# Schematic_OpenBook.net
KiCad netlist of a schematic drawn in EAGLE
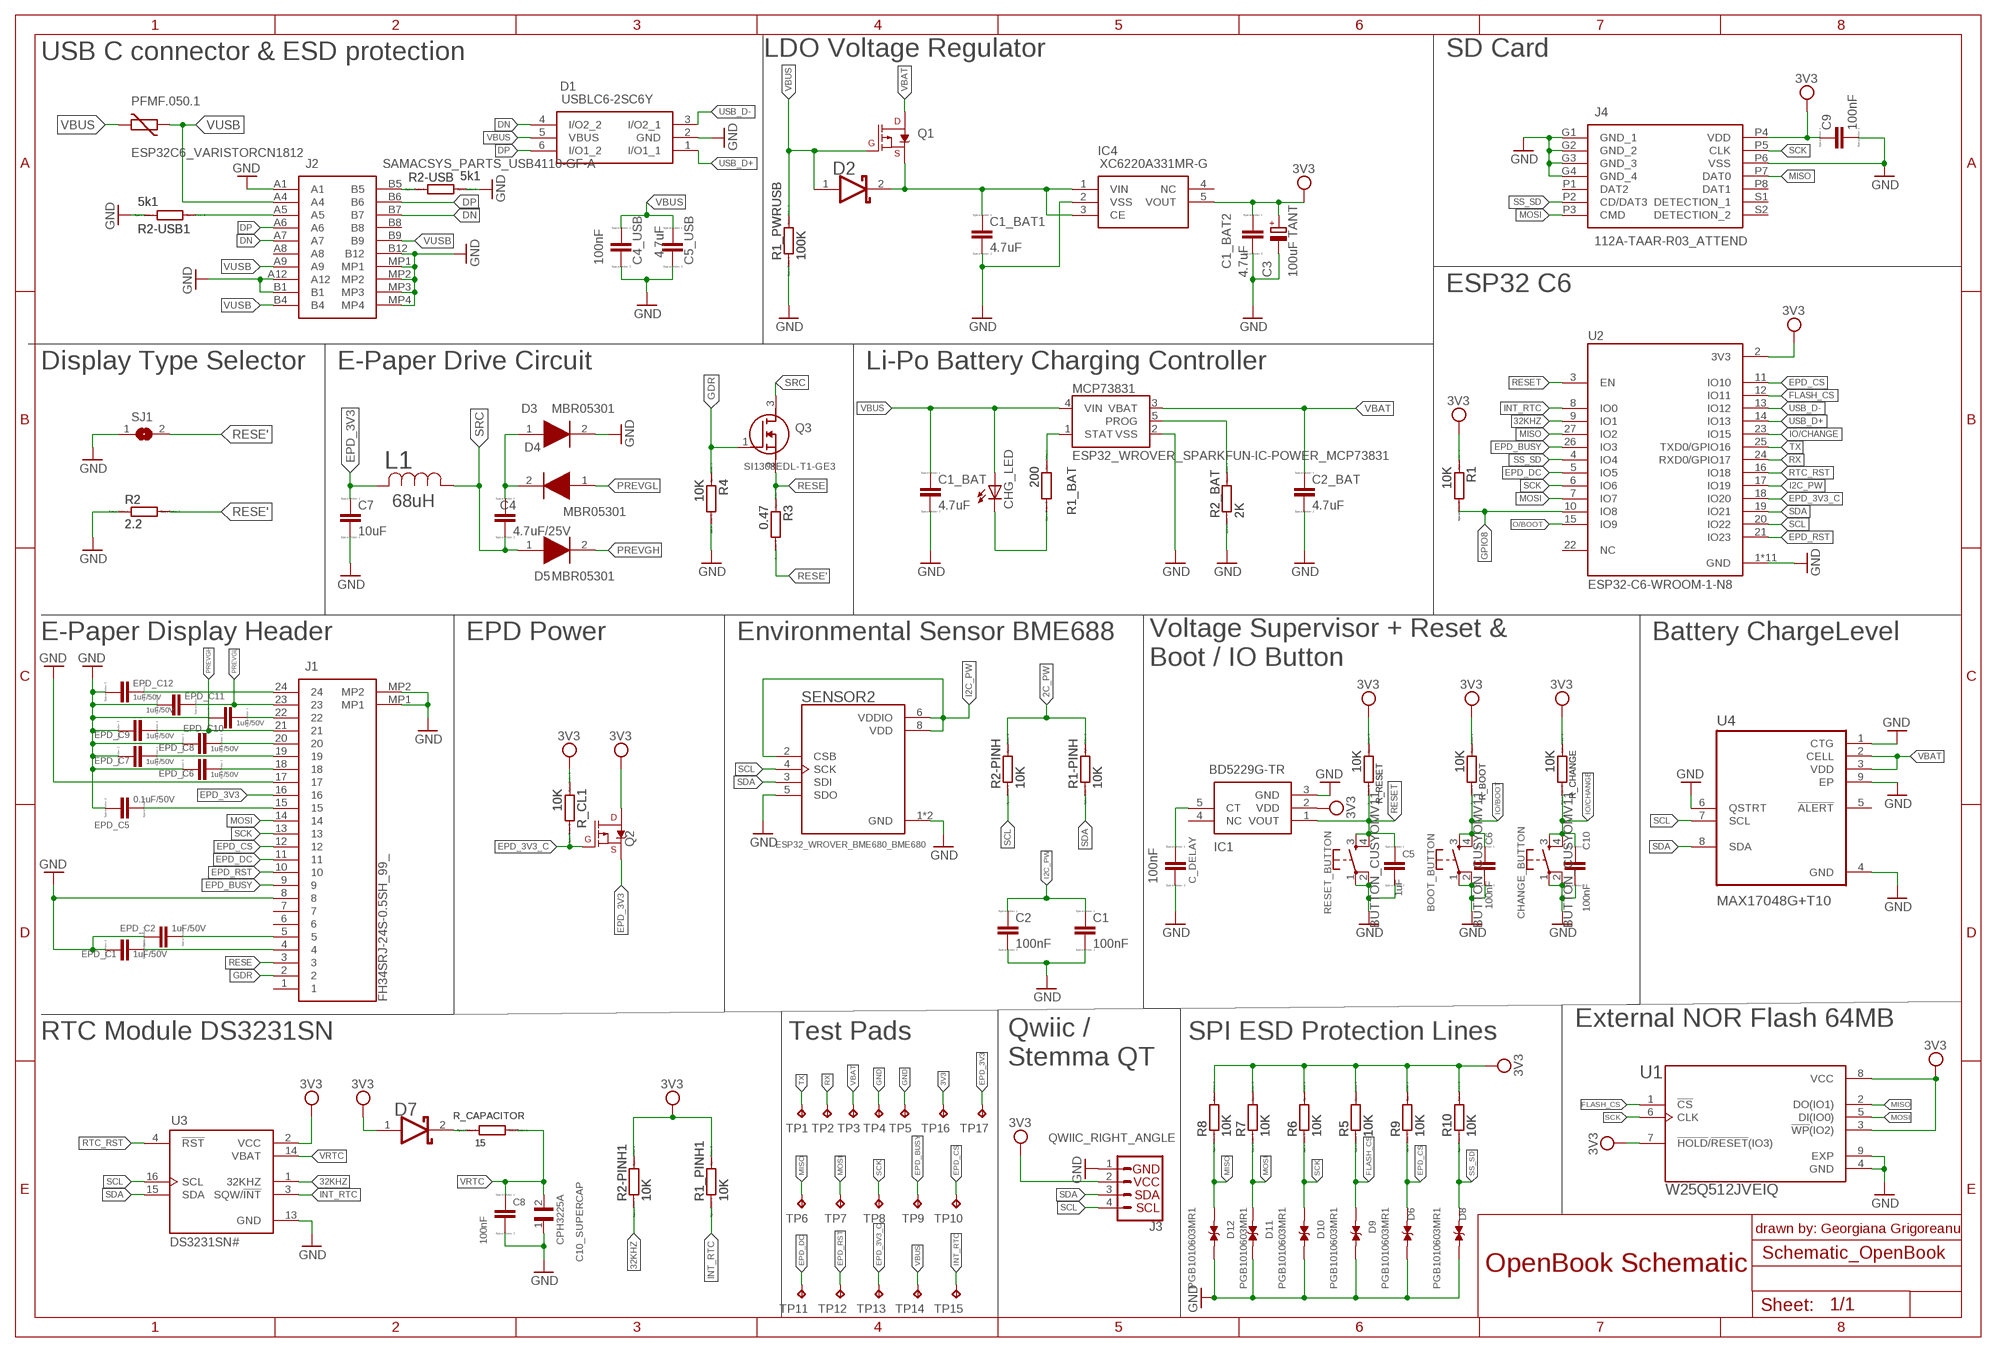
[diagram p0: schematic, sheet 1]

(export (version "E")
  (design (tool "Eeschema 10.0.6"))
  (components
    (comp (ref "BOOT_BUTTON")
      (value "BUTTON_CUSYOMV11")
      (footprint "eagle-import:MYBUTTON")
      (libsource (lib "eagle-import") (part "BUTTON_CUSYOMV11"))
    )
    (comp (ref "C1")
      (value "100nF")
      (footprint "eagle-import:ESP32_WROVER_EAGLE-LTSPICE_C0402")
      (libsource (lib "eagle-import") (part "ESP32_WROVER_EAGLE-LTSPICE_C"))
    )
    (comp (ref "C1_BAT")
      (value "4.7uF")
      (footprint "eagle-import:ESP32_WROVER_EAGLE-LTSPICE_C0402")
      (libsource (lib "eagle-import") (part "ESP32_WROVER_EAGLE-LTSPICE_C"))
    )
    (comp (ref "C1_BAT1")
      (value "4.7uF")
      (footprint "eagle-import:ESP32_WROVER_EAGLE-LTSPICE_C0402")
      (libsource (lib "eagle-import") (part "ESP32_WROVER_EAGLE-LTSPICE_C"))
    )
    (comp (ref "C1_BAT2")
      (value "4.7uF")
      (footprint "eagle-import:ESP32_WROVER_EAGLE-LTSPICE_C0402")
      (libsource (lib "eagle-import") (part "ESP32_WROVER_EAGLE-LTSPICE_C"))
    )
    (comp (ref "C2")
      (value "100nF")
      (footprint "eagle-import:ESP32_WROVER_EAGLE-LTSPICE_C0402")
      (libsource (lib "eagle-import") (part "ESP32_WROVER_EAGLE-LTSPICE_C"))
    )
    (comp (ref "C2_BAT")
      (value "4.7uF")
      (footprint "eagle-import:ESP32_WROVER_EAGLE-LTSPICE_C0402")
      (libsource (lib "eagle-import") (part "ESP32_WROVER_EAGLE-LTSPICE_C"))
    )
    (comp (ref "C3")
      (value "100uF TANT")
      (footprint "eagle-import:RCL_CT3528")
      (libsource (lib "eagle-import") (part "RCL_CPOL-EUCT3528"))
    )
    (comp (ref "C4")
      (value "4.7uF/25V")
      (footprint "eagle-import:ESP32_WROVER_EAGLE-LTSPICE_C0402")
      (libsource (lib "eagle-import") (part "ESP32_WROVER_EAGLE-LTSPICE_C"))
    )
    (comp (ref "C4_USB")
      (value "100nF")
      (footprint "eagle-import:ESP32_WROVER_EAGLE-LTSPICE_C0402")
      (libsource (lib "eagle-import") (part "ESP32_WROVER_EAGLE-LTSPICE_C"))
    )
    (comp (ref "C5")
      (value "1uF")
      (footprint "eagle-import:ESP32_WROVER_EAGLE-LTSPICE_C0402")
      (libsource (lib "eagle-import") (part "ESP32_WROVER_EAGLE-LTSPICE_C"))
    )
    (comp (ref "C5_USB")
      (value "4.7uF")
      (footprint "eagle-import:ESP32_WROVER_EAGLE-LTSPICE_C0402")
      (libsource (lib "eagle-import") (part "ESP32_WROVER_EAGLE-LTSPICE_C"))
    )
    (comp (ref "C6")
      (value "100nF")
      (footprint "eagle-import:ESP32_WROVER_EAGLE-LTSPICE_C0402")
      (libsource (lib "eagle-import") (part "ESP32_WROVER_EAGLE-LTSPICE_C"))
    )
    (comp (ref "C7")
      (value "10uF")
      (footprint "eagle-import:ESP32_WROVER_EAGLE-LTSPICE_C0402")
      (libsource (lib "eagle-import") (part "ESP32_WROVER_EAGLE-LTSPICE_C"))
    )
    (comp (ref "C8")
      (value "100nF")
      (footprint "eagle-import:ESP32_WROVER_EAGLE-LTSPICE_C0402")
      (libsource (lib "eagle-import") (part "ESP32_WROVER_EAGLE-LTSPICE_C"))
    )
    (comp (ref "C9")
      (value "100nF")
      (footprint "eagle-import:ESP32_WROVER_EAGLE-LTSPICE_C0402")
      (libsource (lib "eagle-import") (part "ESP32_WROVER_EAGLE-LTSPICE_C"))
    )
    (comp (ref "C10")
      (value "100nF")
      (footprint "eagle-import:ESP32_WROVER_EAGLE-LTSPICE_C0402")
      (libsource (lib "eagle-import") (part "ESP32_WROVER_EAGLE-LTSPICE_C"))
    )
    (comp (ref "C10_SUPERCAP")
      (value "CPH3225A")
      (footprint "eagle-import:CAPCP3225X100N")
      (fields (field (name "MF") "Seiko Instruments"))
      (libsource (lib "eagle-import") (part "CPH3225A"))
    )
    (comp (ref "CHANGE_BUTTON")
      (value "BUTTON_CUSYOMV11")
      (footprint "eagle-import:MYBUTTON")
      (libsource (lib "eagle-import") (part "BUTTON_CUSYOMV11"))
    )
    (comp (ref "CHG_LED")
      (value "ADAFRUIT_LEDCHIP-LED0603")
      (footprint "eagle-import:ADAFRUIT_CHIP-LED0603")
      (libsource (lib "eagle-import") (part "ADAFRUIT_LEDCHIP-LED0603"))
    )
    (comp (ref "C_DELAY")
      (value "100nF")
      (footprint "eagle-import:ESP32_WROVER_EAGLE-LTSPICE_C0402")
      (libsource (lib "eagle-import") (part "ESP32_WROVER_EAGLE-LTSPICE_C"))
    )
    (comp (ref "D1")
      (value "USBLC6-2SC6Y")
      (footprint "eagle-import:SOT95P280X145-6N")
      (fields (field (name "MF") "STMicroelectronics"))
      (libsource (lib "eagle-import") (part "USBLC6-2SC6Y"))
    )
    (comp (ref "D2")
      (value "ESP32_WROVER_AVX---SD0805S020S1R0_AVX_SD0805S020S1R0_0_0")
      (footprint "eagle-import:ESP32_WROVER_AVX---SD0805S020S1R0_AVX_SD0805S020S1R0_0")
      (libsource (lib "eagle-import") (part "ESP32_WROVER_AVX---SD0805S020S1R0_AVX_SD0805S020S1R0_0_0"))
    )
    (comp (ref "D3")
      (value "MBR05301")
      (footprint "eagle-import:SOD3716X135N")
      (libsource (lib "eagle-import") (part "MBR05301"))
    )
    (comp (ref "D4")
      (value "MBR05301")
      (footprint "eagle-import:SOD3716X135N")
      (libsource (lib "eagle-import") (part "MBR05301"))
    )
    (comp (ref "D5")
      (value "MBR05301")
      (footprint "eagle-import:SOD3716X135N")
      (libsource (lib "eagle-import") (part "MBR05301"))
    )
    (comp (ref "D6")
      (value "PGB1010603MR1")
      (footprint "eagle-import:DIOC1608X36N")
      (libsource (lib "eagle-import") (part "PGB1010603MR1"))
    )
    (comp (ref "D7")
      (value "ESP32_WROVER_AVX---SD0805S020S1R0_AVX_SD0805S020S1R0_0_0")
      (footprint "eagle-import:ESP32_WROVER_AVX---SD0805S020S1R0_AVX_SD0805S020S1R0_0")
      (libsource (lib "eagle-import") (part "ESP32_WROVER_AVX---SD0805S020S1R0_AVX_SD0805S020S1R0_0_0"))
    )
    (comp (ref "D8")
      (value "PGB1010603MR1")
      (footprint "eagle-import:DIOC1608X36N")
      (libsource (lib "eagle-import") (part "PGB1010603MR1"))
    )
    (comp (ref "D9")
      (value "PGB1010603MR1")
      (footprint "eagle-import:DIOC1608X36N")
      (libsource (lib "eagle-import") (part "PGB1010603MR1"))
    )
    (comp (ref "D10")
      (value "PGB1010603MR1")
      (footprint "eagle-import:DIOC1608X36N")
      (libsource (lib "eagle-import") (part "PGB1010603MR1"))
    )
    (comp (ref "D11")
      (value "PGB1010603MR1")
      (footprint "eagle-import:DIOC1608X36N")
      (libsource (lib "eagle-import") (part "PGB1010603MR1"))
    )
    (comp (ref "D12")
      (value "PGB1010603MR1")
      (footprint "eagle-import:DIOC1608X36N")
      (libsource (lib "eagle-import") (part "PGB1010603MR1"))
    )
    (comp (ref "EPD_C1")
      (value "1uF/50V")
      (footprint "eagle-import:ESP32_WROVER_EAGLE-LTSPICE_C0402")
      (libsource (lib "eagle-import") (part "ESP32_WROVER_EAGLE-LTSPICE_C"))
    )
    (comp (ref "EPD_C2")
      (value "1uF/50V")
      (footprint "eagle-import:ESP32_WROVER_EAGLE-LTSPICE_C0402")
      (libsource (lib "eagle-import") (part "ESP32_WROVER_EAGLE-LTSPICE_C"))
    )
    (comp (ref "EPD_C5")
      (value "0.1uF/50V")
      (footprint "eagle-import:ESP32_WROVER_EAGLE-LTSPICE_C0402")
      (libsource (lib "eagle-import") (part "ESP32_WROVER_EAGLE-LTSPICE_C"))
    )
    (comp (ref "EPD_C6")
      (value "1uF/50V")
      (footprint "eagle-import:ESP32_WROVER_EAGLE-LTSPICE_C0402")
      (libsource (lib "eagle-import") (part "ESP32_WROVER_EAGLE-LTSPICE_C"))
    )
    (comp (ref "EPD_C7")
      (value "1uF/50V")
      (footprint "eagle-import:ESP32_WROVER_EAGLE-LTSPICE_C0402")
      (libsource (lib "eagle-import") (part "ESP32_WROVER_EAGLE-LTSPICE_C"))
    )
    (comp (ref "EPD_C8")
      (value "1uF/50V")
      (footprint "eagle-import:ESP32_WROVER_EAGLE-LTSPICE_C0402")
      (libsource (lib "eagle-import") (part "ESP32_WROVER_EAGLE-LTSPICE_C"))
    )
    (comp (ref "EPD_C9")
      (value "1uF/50V")
      (footprint "eagle-import:ESP32_WROVER_EAGLE-LTSPICE_C0402")
      (libsource (lib "eagle-import") (part "ESP32_WROVER_EAGLE-LTSPICE_C"))
    )
    (comp (ref "EPD_C10")
      (value "1uF/50V")
      (footprint "eagle-import:ESP32_WROVER_EAGLE-LTSPICE_C0402")
      (libsource (lib "eagle-import") (part "ESP32_WROVER_EAGLE-LTSPICE_C"))
    )
    (comp (ref "EPD_C11")
      (value "1uF/50V")
      (footprint "eagle-import:ESP32_WROVER_EAGLE-LTSPICE_C0402")
      (libsource (lib "eagle-import") (part "ESP32_WROVER_EAGLE-LTSPICE_C"))
    )
    (comp (ref "EPD_C12")
      (value "1uF/50V")
      (footprint "eagle-import:ESP32_WROVER_EAGLE-LTSPICE_C0402")
      (libsource (lib "eagle-import") (part "ESP32_WROVER_EAGLE-LTSPICE_C"))
    )
    (comp (ref "IC1")
      (value "BD5229G-TR")
      (footprint "eagle-import:SOT95P280X125-5N")
      (fields (field (name "MOUSER_PART_NUMBER") "755-BD5229G-TR"))
      (libsource (lib "eagle-import") (part "BD5229G-TR"))
    )
    (comp (ref "IC4")
      (value "XC6220A331MR-G")
      (footprint "eagle-import:SOT95P280X120-5N")
      (fields (field (name "MOUSER_PART_NUMBER") "865-XC6220A331MR-G"))
      (libsource (lib "eagle-import") (part "XC6220A331MR-G"))
    )
    (comp (ref "J1")
      (value "FH34SRJ-24S-0.5SH_99_")
      (footprint "eagle-import:FH34SRJ24S05SH99")
      (fields
        (field (name "MANUFACTURER_PART_NUMBER") "FH34SRJ-24S-0.5SH(99)")
        (field (name "MOUSER_PART_NUMBER") "798-FH34SRJ24S05SH99")
      )
      (libsource (lib "eagle-import") (part "FH34SRJ-24S-0.5SH_99_"))
    )
    (comp (ref "J2")
      (value "SAMACSYS_PARTS_USB4110-GF-A")
      (footprint "eagle-import:SAMACSYS_PARTS_USB4110GFA")
      (fields
        (field (name "MANUFACTURER_PART_NUMBER") "USB4110-GF-A")
        (field (name "MOUSER_PART_NUMBER") "640-USB4110-GF-A")
      )
      (libsource (lib "eagle-import") (part "SAMACSYS_PARTS_USB4110-GF-A"))
    )
    (comp (ref "J3")
      (value "QWIIC_RIGHT_ANGLE")
      (footprint "eagle-import:JST04_1MM_RA")
      (libsource (lib "eagle-import") (part "QWIIC_CONNECTORJS-1MM"))
    )
    (comp (ref "J4")
      (value "112A-TAAR-R03_ATTEND")
      (footprint "eagle-import:112ATAARR03ATTEND")
      (fields (field (name "MANUFACTURER_PART_NUMBER") "112A-TAAR-R03 ATTEND"))
      (libsource (lib "eagle-import") (part "112A-TAAR-R03_ATTEND"))
    )
    (comp (ref "L1")
      (value "68uH")
      (footprint "eagle-import:IND_4828-WE-TPC_WRE")
      (fields
        (field (name "MANUFACTURER_PART_NUMBER") "744043680")
        (field (name "COPYRIGHT") "Copyright (C) 2024 Ultra Librarian. All rights reserved.")
      )
      (libsource (lib "eagle-import") (part "744043680IND_4828-WE-TPC_WRE"))
    )
    (comp (ref "MCP73831")
      (value "ESP32_WROVER_SPARKFUN-IC-POWER_MCP73831")
      (footprint "eagle-import:ESP32_WROVER_SPARKFUN-IC-POWER_SOT23-5")
      (libsource (lib "eagle-import") (part "ESP32_WROVER_SPARKFUN-IC-POWER_MCP73831"))
    )
    (comp (ref "PFMF.050.1")
      (value "ESP32C6_VARISTORCN1812")
      (footprint "eagle-import:ESP32C6_VARISTOR_CT_CN1812")
      (libsource (lib "eagle-import") (part "ESP32C6_VARISTORCN1812"))
    )
    (comp (ref "Q1")
      (value "20V/4.2A/52mΩ/1.4W")
      (footprint "eagle-import:ESP32_WROVER_SPARKFUN-DISCRETESEMI_SOT23-3")
      (libsource (lib "eagle-import") (part "ESP32_WROVER_SPARKFUN-DISCRETESEMI_MOSFET_PCH"))
    )
    (comp (ref "Q2")
      (value "20V/4.2A/52mΩ/1.4W")
      (footprint "eagle-import:ESP32_WROVER_SPARKFUN-DISCRETESEMI_SOT23-3")
      (libsource (lib "eagle-import") (part "ESP32_WROVER_SPARKFUN-DISCRETESEMI_MOSFET_PCH"))
    )
    (comp (ref "Q3")
      (value "SI1308EDL-T1-GE3")
      (footprint "eagle-import:SOT65P210X110-3N")
      (fields (field (name "MF") "Vishay Siliconix"))
      (libsource (lib "eagle-import") (part "SI1308EDL-T1-GE3"))
    )
    (comp (ref "R1")
      (value "10K")
      (footprint "eagle-import:ESP32_WROVER_EAGLE-LTSPICE_C0402")
      (libsource (lib "eagle-import") (part "ESP32_WROVER_EAGLE-LTSPICE_R1"))
    )
    (comp (ref "R1-PINH")
      (value "10K")
      (footprint "eagle-import:ESP32_WROVER_EAGLE-LTSPICE_C0402")
      (libsource (lib "eagle-import") (part "ESP32_WROVER_EAGLE-LTSPICE_R1"))
    )
    (comp (ref "R1_BAT")
      (value "200")
      (footprint "eagle-import:ESP32_WROVER_EAGLE-LTSPICE_C0402")
      (libsource (lib "eagle-import") (part "ESP32_WROVER_EAGLE-LTSPICE_R1"))
    )
    (comp (ref "R1_PINH1")
      (value "10K")
      (footprint "eagle-import:ESP32_WROVER_EAGLE-LTSPICE_C0402")
      (libsource (lib "eagle-import") (part "ESP32_WROVER_EAGLE-LTSPICE_R1"))
    )
    (comp (ref "R1_PWRUSB")
      (value "100K")
      (footprint "eagle-import:ESP32_WROVER_EAGLE-LTSPICE_C0402")
      (libsource (lib "eagle-import") (part "ESP32_WROVER_EAGLE-LTSPICE_R1"))
    )
    (comp (ref "R2")
      (value "2.2")
      (footprint "eagle-import:ESP32_WROVER_EAGLE-LTSPICE_C0402")
      (libsource (lib "eagle-import") (part "ESP32_WROVER_EAGLE-LTSPICE_R1"))
    )
    (comp (ref "R2-PINH")
      (value "10K")
      (footprint "eagle-import:ESP32_WROVER_EAGLE-LTSPICE_C0402")
      (libsource (lib "eagle-import") (part "ESP32_WROVER_EAGLE-LTSPICE_R1"))
    )
    (comp (ref "R2-PINH1")
      (value "10K")
      (footprint "eagle-import:ESP32_WROVER_EAGLE-LTSPICE_C0402")
      (libsource (lib "eagle-import") (part "ESP32_WROVER_EAGLE-LTSPICE_R1"))
    )
    (comp (ref "R2-USB")
      (value "5k1")
      (footprint "eagle-import:ESP32_WROVER_EAGLE-LTSPICE_C0402")
      (libsource (lib "eagle-import") (part "ESP32_WROVER_EAGLE-LTSPICE_R1"))
    )
    (comp (ref "R2-USB1")
      (value "5k1")
      (footprint "eagle-import:ESP32_WROVER_EAGLE-LTSPICE_C0402")
      (libsource (lib "eagle-import") (part "ESP32_WROVER_EAGLE-LTSPICE_R1"))
    )
    (comp (ref "R2_BAT")
      (value "2K")
      (footprint "eagle-import:ESP32_WROVER_EAGLE-LTSPICE_C0402")
      (libsource (lib "eagle-import") (part "ESP32_WROVER_EAGLE-LTSPICE_R1"))
    )
    (comp (ref "R3")
      (value "0.47")
      (footprint "eagle-import:ESP32_WROVER_EAGLE-LTSPICE_C0402")
      (libsource (lib "eagle-import") (part "ESP32_WROVER_EAGLE-LTSPICE_R1"))
    )
    (comp (ref "R4")
      (value "10K")
      (footprint "eagle-import:ESP32_WROVER_EAGLE-LTSPICE_C0402")
      (libsource (lib "eagle-import") (part "ESP32_WROVER_EAGLE-LTSPICE_R1"))
    )
    (comp (ref "R5")
      (value "10K")
      (footprint "eagle-import:ESP32_WROVER_EAGLE-LTSPICE_C0402")
      (libsource (lib "eagle-import") (part "ESP32_WROVER_EAGLE-LTSPICE_R1"))
    )
    (comp (ref "R6")
      (value "10K")
      (footprint "eagle-import:ESP32_WROVER_EAGLE-LTSPICE_C0402")
      (libsource (lib "eagle-import") (part "ESP32_WROVER_EAGLE-LTSPICE_R1"))
    )
    (comp (ref "R7")
      (value "10K")
      (footprint "eagle-import:ESP32_WROVER_EAGLE-LTSPICE_C0402")
      (libsource (lib "eagle-import") (part "ESP32_WROVER_EAGLE-LTSPICE_R1"))
    )
    (comp (ref "R8")
      (value "10K")
      (footprint "eagle-import:ESP32_WROVER_EAGLE-LTSPICE_C0402")
      (libsource (lib "eagle-import") (part "ESP32_WROVER_EAGLE-LTSPICE_R1"))
    )
    (comp (ref "R9")
      (value "10K")
      (footprint "eagle-import:ESP32_WROVER_EAGLE-LTSPICE_C0402")
      (libsource (lib "eagle-import") (part "ESP32_WROVER_EAGLE-LTSPICE_R1"))
    )
    (comp (ref "R10")
      (value "10K")
      (footprint "eagle-import:ESP32_WROVER_EAGLE-LTSPICE_C0402")
      (libsource (lib "eagle-import") (part "ESP32_WROVER_EAGLE-LTSPICE_R1"))
    )
    (comp (ref "RESET_BUTTON")
      (value "BUTTON_CUSYOMV11")
      (footprint "eagle-import:MYBUTTON")
      (libsource (lib "eagle-import") (part "BUTTON_CUSYOMV11"))
    )
    (comp (ref "R_BOOT")
      (value "10K")
      (footprint "eagle-import:ESP32_WROVER_EAGLE-LTSPICE_C0402")
      (libsource (lib "eagle-import") (part "ESP32_WROVER_EAGLE-LTSPICE_R1"))
    )
    (comp (ref "R_CAPACITOR")
      (value "15")
      (footprint "eagle-import:ESP32_WROVER_EAGLE-LTSPICE_C0402")
      (libsource (lib "eagle-import") (part "ESP32_WROVER_EAGLE-LTSPICE_R1"))
    )
    (comp (ref "R_CHANGE")
      (value "10K")
      (footprint "eagle-import:ESP32_WROVER_EAGLE-LTSPICE_C0402")
      (libsource (lib "eagle-import") (part "ESP32_WROVER_EAGLE-LTSPICE_R1"))
    )
    (comp (ref "R_CL1")
      (value "10K")
      (footprint "eagle-import:ESP32_WROVER_EAGLE-LTSPICE_C0402")
      (libsource (lib "eagle-import") (part "ESP32_WROVER_EAGLE-LTSPICE_R1"))
    )
    (comp (ref "R_RESET")
      (value "10K")
      (footprint "eagle-import:ESP32_WROVER_EAGLE-LTSPICE_C0402")
      (libsource (lib "eagle-import") (part "ESP32_WROVER_EAGLE-LTSPICE_R1"))
    )
    (comp (ref "SENSOR2")
      (value "ESP32_WROVER_BME680_BME680")
      (footprint "eagle-import:ESP32_WROVER_BME680_PSON80P300X300X100-8N")
      (fields (field (name "MF") "Bosch Sensortec") (field (name "MP") "BME680"))
      (libsource (lib "eagle-import") (part "ESP32_WROVER_BME680_BME680"))
    )
    (comp (ref "SJ1") (value "SJ") (footprint "eagle-import:SJ") (libsource (lib "eagle-import") (part "SJ")))
    (comp (ref "TP1")
      (value "TP")
      (footprint "eagle-import:TP20R")
      (libsource (lib "eagle-import") (part "TP"))
    )
    (comp (ref "TP2")
      (value "TP")
      (footprint "eagle-import:TP20R")
      (libsource (lib "eagle-import") (part "TP"))
    )
    (comp (ref "TP3")
      (value "TP")
      (footprint "eagle-import:TP20R")
      (libsource (lib "eagle-import") (part "TP"))
    )
    (comp (ref "TP4")
      (value "TP")
      (footprint "eagle-import:TP20R")
      (libsource (lib "eagle-import") (part "TP"))
    )
    (comp (ref "TP5")
      (value "TP")
      (footprint "eagle-import:TP20R")
      (libsource (lib "eagle-import") (part "TP"))
    )
    (comp (ref "TP6")
      (value "TP")
      (footprint "eagle-import:TP20R")
      (libsource (lib "eagle-import") (part "TP"))
    )
    (comp (ref "TP7")
      (value "TP")
      (footprint "eagle-import:TP20R")
      (libsource (lib "eagle-import") (part "TP"))
    )
    (comp (ref "TP8")
      (value "TP")
      (footprint "eagle-import:TP20R")
      (libsource (lib "eagle-import") (part "TP"))
    )
    (comp (ref "TP9")
      (value "TP")
      (footprint "eagle-import:TP20R")
      (libsource (lib "eagle-import") (part "TP"))
    )
    (comp (ref "TP10")
      (value "TP")
      (footprint "eagle-import:TP20R")
      (libsource (lib "eagle-import") (part "TP"))
    )
    (comp (ref "TP11")
      (value "TP")
      (footprint "eagle-import:TP20R")
      (libsource (lib "eagle-import") (part "TP"))
    )
    (comp (ref "TP12")
      (value "TP")
      (footprint "eagle-import:TP20R")
      (libsource (lib "eagle-import") (part "TP"))
    )
    (comp (ref "TP13")
      (value "TP")
      (footprint "eagle-import:TP20R")
      (libsource (lib "eagle-import") (part "TP"))
    )
    (comp (ref "TP14")
      (value "TP")
      (footprint "eagle-import:TP20R")
      (libsource (lib "eagle-import") (part "TP"))
    )
    (comp (ref "TP15")
      (value "TP")
      (footprint "eagle-import:TP20R")
      (libsource (lib "eagle-import") (part "TP"))
    )
    (comp (ref "TP16")
      (value "TP")
      (footprint "eagle-import:TP20R")
      (libsource (lib "eagle-import") (part "TP"))
    )
    (comp (ref "TP17")
      (value "TP")
      (footprint "eagle-import:TP20R")
      (libsource (lib "eagle-import") (part "TP"))
    )
    (comp (ref "U1")
      (value "W25Q512JVEIQ")
      (footprint "eagle-import:SON127P600X800X80-9N")
      (fields (field (name "MF") "Winbond Electronics"))
      (libsource (lib "eagle-import") (part "W25Q512JVEIQ"))
    )
    (comp (ref "U2")
      (value "ESP32-C6-WROOM-1-N8")
      (footprint "eagle-import:XCVR_ESP32-C6-WROOM-1-N8")
      (fields (field (name "MF") "Espressif Systems"))
      (libsource (lib "eagle-import") (part "ESP32-C6-WROOM-1-N8"))
    )
    (comp (ref "U3")
      (value "DS3231SN#")
      (footprint "eagle-import:SOIC127P1032X265-16N")
      (fields (field (name "MF") "Analog Devices"))
      (libsource (lib "eagle-import") (part "DS3231SN#"))
    )
    (comp (ref "U4")
      (value "MAX17048G+T10")
      (footprint "eagle-import:SON50P200X200X80-9N")
      (fields (field (name "MF") "Analog Devices"))
      (libsource (lib "eagle-import") (part "MAX17048G+T10"))
    )
  )
  (nets
    (net (code "1") (name "2C_PW") (class "Default")
      (node (ref "R1-PINH") (pin "2") (pinfunction "2_2") (pintype "passive"))
      (node (ref "R2-PINH") (pin "2") (pinfunction "2_2") (pintype "passive"))
    )
    (net (code "2") (name "3V3") (class "Default")
      (node (ref "C1_BAT2") (pin "1") (pinfunction "1_1") (pintype "passive"))
      (node (ref "C3") (pin "+") (pinfunction "+_+") (pintype "passive"))
      (node (ref "C9") (pin "1") (pinfunction "1_1") (pintype "passive"))
      (node (ref "D7") (pin "1") (pinfunction "ANODE_1") (pintype "bidirectional"))
      (node (ref "IC1") (pin "2") (pinfunction "VDD_2") (pintype "bidirectional"))
      (node (ref "IC4") (pin "5") (pinfunction "VOUT_5") (pintype "bidirectional"))
      (node (ref "J3") (pin "2") (pinfunction "2_2") (pintype "power_in"))
      (node (ref "J4") (pin "P4") (pinfunction "VDD_P4") (pintype "bidirectional"))
      (node (ref "Q2") (pin "1") (pinfunction "D_1") (pintype "bidirectional"))
      (node (ref "R1") (pin "1") (pinfunction "1_1") (pintype "passive"))
      (node (ref "R10") (pin "2") (pinfunction "2_2") (pintype "passive"))
      (node (ref "R1_PINH1") (pin "2") (pinfunction "2_2") (pintype "passive"))
      (node (ref "R2-PINH1") (pin "2") (pinfunction "2_2") (pintype "passive"))
      (node (ref "R5") (pin "2") (pinfunction "2_2") (pintype "passive"))
      (node (ref "R6") (pin "2") (pinfunction "2_2") (pintype "passive"))
      (node (ref "R7") (pin "2") (pinfunction "2_2") (pintype "passive"))
      (node (ref "R8") (pin "2") (pinfunction "2_2") (pintype "passive"))
      (node (ref "R9") (pin "2") (pinfunction "2_2") (pintype "passive"))
      (node (ref "R_BOOT") (pin "1") (pinfunction "1_1") (pintype "passive"))
      (node (ref "R_CHANGE") (pin "1") (pinfunction "1_1") (pintype "passive"))
      (node (ref "R_CL1") (pin "1") (pinfunction "1_1") (pintype "passive"))
      (node (ref "R_RESET") (pin "1") (pinfunction "1_1") (pintype "passive"))
      (node (ref "TP16") (pin "TP") (pinfunction "TP_TP") (pintype "input"))
      (node (ref "U1") (pin "3") (pinfunction "~{WP}(IO2)_3") (pintype "bidirectional"))
      (node (ref "U1") (pin "7") (pinfunction "~{HOLD}/~{RESET}(IO3)_7") (pintype "bidirectional"))
      (node (ref "U1") (pin "8") (pinfunction "VCC_8") (pintype "power_in"))
      (node (ref "U2") (pin "2") (pinfunction "3V3_2") (pintype "power_in"))
      (node (ref "U3") (pin "2") (pinfunction "VCC_2") (pintype "power_in"))
    )
    (net (code "3") (name "32KHZ") (class "Default")
      (node (ref "R2-PINH1") (pin "1") (pinfunction "1_1") (pintype "passive"))
      (node (ref "U2") (pin "9") (pinfunction "IO1_9") (pintype "bidirectional"))
      (node (ref "U3") (pin "1") (pinfunction "32KHZ_1") (pintype "output"))
    )
    (net (code "4") (name "DN") (class "Default")
      (node (ref "D1") (pin "4") (pinfunction "I/O2_2_4") (pintype "bidirectional"))
      (node (ref "J2") (pin "A7") (pinfunction "A7_A7") (pintype "bidirectional"))
      (node (ref "J2") (pin "B7") (pinfunction "B7_B7") (pintype "bidirectional"))
    )
    (net (code "5") (name "DP") (class "Default")
      (node (ref "D1") (pin "6") (pinfunction "I/O1_2_6") (pintype "bidirectional"))
      (node (ref "J2") (pin "A6") (pinfunction "A6_A6") (pintype "bidirectional"))
      (node (ref "J2") (pin "B6") (pinfunction "B6_B6") (pintype "bidirectional"))
    )
    (net (code "6") (name "EPD_3V3") (class "Default")
      (node (ref "C7") (pin "1") (pinfunction "1_1") (pintype "passive"))
      (node (ref "J1") (pin "16") (pinfunction "16_16") (pintype "bidirectional"))
      (node (ref "L1") (pin "2") (pinfunction "2_2") (pintype "passive"))
      (node (ref "Q2") (pin "3") (pinfunction "S_3") (pintype "bidirectional"))
      (node (ref "TP17") (pin "TP") (pinfunction "TP_TP") (pintype "input"))
    )
    (net (code "7") (name "EPD_3V3_C") (class "Default")
      (node (ref "Q2") (pin "2") (pinfunction "G_2") (pintype "bidirectional"))
      (node (ref "R_CL1") (pin "2") (pinfunction "2_2") (pintype "passive"))
      (node (ref "TP13") (pin "TP") (pinfunction "TP_TP") (pintype "input"))
      (node (ref "U2") (pin "18") (pinfunction "IO20_18") (pintype "bidirectional"))
    )
    (net (code "8") (name "EPD_BUSY") (class "Default")
      (node (ref "J1") (pin "9") (pinfunction "9_9") (pintype "bidirectional"))
      (node (ref "TP9") (pin "TP") (pinfunction "TP_TP") (pintype "input"))
      (node (ref "U2") (pin "26") (pinfunction "IO3_26") (pintype "bidirectional"))
    )
    (net (code "9") (name "EPD_CS") (class "Default")
      (node (ref "D6") (pin "1") (pinfunction "1_1") (pintype "passive"))
      (node (ref "J1") (pin "12") (pinfunction "12_12") (pintype "bidirectional"))
      (node (ref "R9") (pin "1") (pinfunction "1_1") (pintype "passive"))
      (node (ref "TP10") (pin "TP") (pinfunction "TP_TP") (pintype "input"))
      (node (ref "U2") (pin "11") (pinfunction "IO10_11") (pintype "bidirectional"))
    )
    (net (code "10") (name "EPD_DC") (class "Default")
      (node (ref "J1") (pin "11") (pinfunction "11_11") (pintype "bidirectional"))
      (node (ref "TP11") (pin "TP") (pinfunction "TP_TP") (pintype "input"))
      (node (ref "U2") (pin "5") (pinfunction "IO5_5") (pintype "bidirectional"))
    )
    (net (code "11") (name "EPD_RST") (class "Default")
      (node (ref "J1") (pin "10") (pinfunction "10_10") (pintype "bidirectional"))
      (node (ref "TP12") (pin "TP") (pinfunction "TP_TP") (pintype "input"))
      (node (ref "U2") (pin "21") (pinfunction "IO23_21") (pintype "bidirectional"))
    )
    (net (code "12") (name "FLASH_CS") (class "Default")
      (node (ref "D9") (pin "1") (pinfunction "1_1") (pintype "passive"))
      (node (ref "R5") (pin "1") (pinfunction "1_1") (pintype "passive"))
      (node (ref "U1") (pin "1") (pinfunction "~{CS}_1") (pintype "input"))
      (node (ref "U2") (pin "12") (pinfunction "IO11_12") (pintype "bidirectional"))
    )
    (net (code "13") (name "GDR") (class "Default")
      (node (ref "J1") (pin "2") (pinfunction "2_2") (pintype "bidirectional"))
      (node (ref "Q3") (pin "1") (pinfunction "G_1") (pintype "bidirectional"))
      (node (ref "R4") (pin "1") (pinfunction "1_1") (pintype "passive"))
    )
    (net (code "14") (name "GND") (class "Default")
      (node (ref "BOOT_BUTTON") (pin "1") (pinfunction "1_1") (pintype "passive"))
      (node (ref "BOOT_BUTTON") (pin "2") (pinfunction "2_2") (pintype "passive"))
      (node (ref "C1") (pin "2") (pinfunction "2_2") (pintype "passive"))
      (node (ref "C10") (pin "2") (pinfunction "2_2") (pintype "passive"))
      (node (ref "C10_SUPERCAP") (pin "1") (pinfunction "1_1") (pintype "passive"))
      (node (ref "C1_BAT") (pin "2") (pinfunction "2_2") (pintype "passive"))
      (node (ref "C1_BAT1") (pin "2") (pinfunction "2_2") (pintype "passive"))
      (node (ref "C1_BAT2") (pin "2") (pinfunction "2_2") (pintype "passive"))
      (node (ref "C2") (pin "2") (pinfunction "2_2") (pintype "passive"))
      (node (ref "C2_BAT") (pin "2") (pinfunction "2_2") (pintype "passive"))
      (node (ref "C3") (pin "-") (pinfunction "-_-") (pintype "passive"))
      (node (ref "C4_USB") (pin "2") (pinfunction "2_2") (pintype "passive"))
      (node (ref "C5") (pin "2") (pinfunction "2_2") (pintype "passive"))
      (node (ref "C5_USB") (pin "2") (pinfunction "2_2") (pintype "passive"))
      (node (ref "C6") (pin "2") (pinfunction "2_2") (pintype "passive"))
      (node (ref "C7") (pin "2") (pinfunction "2_2") (pintype "passive"))
      (node (ref "C8") (pin "2") (pinfunction "2_2") (pintype "passive"))
      (node (ref "C9") (pin "2") (pinfunction "2_2") (pintype "passive"))
      (node (ref "CHANGE_BUTTON") (pin "1") (pinfunction "1_1") (pintype "passive"))
      (node (ref "CHANGE_BUTTON") (pin "2") (pinfunction "2_2") (pintype "passive"))
      (node (ref "C_DELAY") (pin "2") (pinfunction "2_2") (pintype "passive"))
      (node (ref "D1") (pin "2") (pinfunction "GND_2") (pintype "bidirectional"))
      (node (ref "D10") (pin "2") (pinfunction "2_2") (pintype "passive"))
      (node (ref "D11") (pin "2") (pinfunction "2_2") (pintype "passive"))
      (node (ref "D12") (pin "2") (pinfunction "2_2") (pintype "passive"))
      (node (ref "D3") (pin "2") (pinfunction "K_2") (pintype "bidirectional"))
      (node (ref "D6") (pin "2") (pinfunction "2_2") (pintype "passive"))
      (node (ref "D8") (pin "2") (pinfunction "2_2") (pintype "passive"))
      (node (ref "D9") (pin "2") (pinfunction "2_2") (pintype "passive"))
      (node (ref "EPD_C1") (pin "2") (pinfunction "2_2") (pintype "passive"))
      (node (ref "EPD_C10") (pin "2") (pinfunction "2_2") (pintype "passive"))
      (node (ref "EPD_C11") (pin "2") (pinfunction "2_2") (pintype "passive"))
      (node (ref "EPD_C12") (pin "2") (pinfunction "2_2") (pintype "passive"))
      (node (ref "EPD_C2") (pin "2") (pinfunction "2_2") (pintype "passive"))
      (node (ref "EPD_C5") (pin "2") (pinfunction "2_2") (pintype "passive"))
      (node (ref "EPD_C6") (pin "2") (pinfunction "2_2") (pintype "passive"))
      (node (ref "EPD_C7") (pin "2") (pinfunction "2_2") (pintype "passive"))
      (node (ref "EPD_C8") (pin "2") (pinfunction "2_2") (pintype "passive"))
      (node (ref "EPD_C9") (pin "2") (pinfunction "2_2") (pintype "passive"))
      (node (ref "IC1") (pin "3") (pinfunction "GND_3") (pintype "bidirectional"))
      (node (ref "IC4") (pin "2") (pinfunction "VSS_2") (pintype "bidirectional"))
      (node (ref "J1") (pin "17") (pinfunction "17_17") (pintype "bidirectional"))
      (node (ref "J1") (pin "8") (pinfunction "8_8") (pintype "bidirectional"))
      (node (ref "J1") (pin "MP1") (pinfunction "MP1_MP1") (pintype "bidirectional"))
      (node (ref "J1") (pin "MP2") (pinfunction "MP2_MP2") (pintype "bidirectional"))
      (node (ref "J2") (pin "A1") (pinfunction "A1_A1") (pintype "bidirectional"))
      (node (ref "J2") (pin "A12") (pinfunction "A12_A12") (pintype "bidirectional"))
      (node (ref "J2") (pin "B1") (pinfunction "B1_B1") (pintype "bidirectional"))
      (node (ref "J2") (pin "B12") (pinfunction "B12_B12") (pintype "bidirectional"))
      (node (ref "J2") (pin "MP1") (pinfunction "MP1_MP1") (pintype "bidirectional"))
      (node (ref "J2") (pin "MP2") (pinfunction "MP2_MP2") (pintype "bidirectional"))
      (node (ref "J2") (pin "MP3") (pinfunction "MP3_MP3") (pintype "bidirectional"))
      (node (ref "J2") (pin "MP4") (pinfunction "MP4_MP4") (pintype "bidirectional"))
      (node (ref "J3") (pin "1") (pinfunction "1_1") (pintype "power_in"))
      (node (ref "J4") (pin "G1") (pinfunction "GND_1_G1") (pintype "bidirectional"))
      (node (ref "J4") (pin "G2") (pinfunction "GND_2_G2") (pintype "bidirectional"))
      (node (ref "J4") (pin "G3") (pinfunction "GND_3_G3") (pintype "bidirectional"))
      (node (ref "J4") (pin "G4") (pinfunction "GND_4_G4") (pintype "bidirectional"))
      (node (ref "J4") (pin "P6") (pinfunction "VSS_P6") (pintype "bidirectional"))
      (node (ref "MCP73831") (pin "2") (pinfunction "VSS_2") (pintype "power_in"))
      (node (ref "R1_PWRUSB") (pin "1") (pinfunction "1_1") (pintype "passive"))
      (node (ref "R2") (pin "1") (pinfunction "1_1") (pintype "passive"))
      (node (ref "R2-USB") (pin "2") (pinfunction "2_2") (pintype "passive"))
      (node (ref "R2-USB1") (pin "1") (pinfunction "1_1") (pintype "passive"))
      (node (ref "R2_BAT") (pin "1") (pinfunction "1_1") (pintype "passive"))
      (node (ref "R4") (pin "2") (pinfunction "2_2") (pintype "passive"))
      (node (ref "RESET_BUTTON") (pin "1") (pinfunction "1_1") (pintype "passive"))
      (node (ref "RESET_BUTTON") (pin "2") (pinfunction "2_2") (pintype "passive"))
      (node (ref "SENSOR2") (pin "1") (pinfunction "GND_1") (pintype "power_in"))
      (node (ref "SENSOR2") (pin "5") (pinfunction "SDO_5") (pintype "bidirectional"))
      (node (ref "SENSOR2") (pin "7") (pinfunction "GND_7") (pintype "power_in"))
      (node (ref "SJ1") (pin "1") (pinfunction "1_1") (pintype "passive"))
      (node (ref "TP4") (pin "TP") (pinfunction "TP_TP") (pintype "input"))
      (node (ref "TP5") (pin "TP") (pinfunction "TP_TP") (pintype "input"))
      (node (ref "U1") (pin "4") (pinfunction "GND_4") (pintype "power_in"))
      (node (ref "U1") (pin "9") (pinfunction "EXP_9") (pintype "passive"))
      (node (ref "U2") (pin "1") (pinfunction "GND_1") (pintype "power_in"))
      (node (ref "U2") (pin "28") (pinfunction "GND_28") (pintype "power_in"))
      (node (ref "U2") (pin "29_1") (pinfunction "GND_29_1") (pintype "power_in"))
      (node (ref "U2") (pin "29_2") (pinfunction "GND_29_2") (pintype "power_in"))
      (node (ref "U2") (pin "29_3") (pinfunction "GND_29_3") (pintype "power_in"))
      (node (ref "U2") (pin "29_4") (pinfunction "GND_29_4") (pintype "power_in"))
      (node (ref "U2") (pin "29_5") (pinfunction "GND_29_5") (pintype "power_in"))
      (node (ref "U2") (pin "29_6") (pinfunction "GND_29_6") (pintype "power_in"))
      (node (ref "U2") (pin "29_7") (pinfunction "GND_29_7") (pintype "power_in"))
      (node (ref "U2") (pin "29_8") (pinfunction "GND_29_8") (pintype "power_in"))
      (node (ref "U2") (pin "29_9") (pinfunction "GND_29_9") (pintype "power_in"))
      (node (ref "U3") (pin "13") (pinfunction "GND_13") (pintype "power_in"))
      (node (ref "U4") (pin "1") (pinfunction "CTG_1") (pintype "power_in"))
      (node (ref "U4") (pin "4") (pinfunction "GND_4") (pintype "power_in"))
      (node (ref "U4") (pin "6") (pinfunction "QSTRT_6") (pintype "input"))
      (node (ref "U4") (pin "9") (pinfunction "EP_9") (pintype "power_in"))
    )
    (net (code "15") (name "GPIO8") (class "Default")
      (node (ref "R1") (pin "2") (pinfunction "2_2") (pintype "passive"))
      (node (ref "U2") (pin "10") (pinfunction "IO8_10") (pintype "bidirectional"))
    )
    (net (code "16") (name "I2C_PW") (class "Default")
      (node (ref "C1") (pin "1") (pinfunction "1_1") (pintype "passive"))
      (node (ref "C2") (pin "1") (pinfunction "1_1") (pintype "passive"))
      (node (ref "SENSOR2") (pin "2") (pinfunction "CSB_2") (pintype "input"))
      (node (ref "SENSOR2") (pin "6") (pinfunction "VDDIO_6") (pintype "power_in"))
      (node (ref "SENSOR2") (pin "8") (pinfunction "VDD_8") (pintype "power_in"))
      (node (ref "U2") (pin "17") (pinfunction "IO19_17") (pintype "bidirectional"))
    )
    (net (code "17") (name "INT_RTC") (class "Default")
      (node (ref "R1_PINH1") (pin "1") (pinfunction "1_1") (pintype "passive"))
      (node (ref "TP15") (pin "TP") (pinfunction "TP_TP") (pintype "input"))
      (node (ref "U2") (pin "8") (pinfunction "IO0_8") (pintype "bidirectional"))
      (node (ref "U3") (pin "3") (pinfunction "SQW/~{INT}_3") (pintype "output"))
    )
    (net (code "18") (name "IO{slash}BOOT") (class "Default")
      (node (ref "BOOT_BUTTON") (pin "3") (pinfunction "3_3") (pintype "passive"))
      (node (ref "BOOT_BUTTON") (pin "4") (pinfunction "4_4") (pintype "passive"))
      (node (ref "C6") (pin "1") (pinfunction "1_1") (pintype "passive"))
      (node (ref "R_BOOT") (pin "2") (pinfunction "2_2") (pintype "passive"))
      (node (ref "U2") (pin "15") (pinfunction "IO9_15") (pintype "bidirectional"))
    )
    (net (code "19") (name "IO{slash}CHANGE") (class "Default")
      (node (ref "C10") (pin "1") (pinfunction "1_1") (pintype "passive"))
      (node (ref "CHANGE_BUTTON") (pin "3") (pinfunction "3_3") (pintype "passive"))
      (node (ref "CHANGE_BUTTON") (pin "4") (pinfunction "4_4") (pintype "passive"))
      (node (ref "R_CHANGE") (pin "2") (pinfunction "2_2") (pintype "passive"))
      (node (ref "U2") (pin "23") (pinfunction "IO15_23") (pintype "bidirectional"))
    )
    (net (code "20") (name "MISO") (class "Default")
      (node (ref "D12") (pin "1") (pinfunction "1_1") (pintype "passive"))
      (node (ref "J4") (pin "P7") (pinfunction "DAT0_P7") (pintype "bidirectional"))
      (node (ref "R8") (pin "1") (pinfunction "1_1") (pintype "passive"))
      (node (ref "TP6") (pin "TP") (pinfunction "TP_TP") (pintype "input"))
      (node (ref "U1") (pin "2") (pinfunction "DO(IO1)_2") (pintype "bidirectional"))
      (node (ref "U2") (pin "27") (pinfunction "IO2_27") (pintype "bidirectional"))
    )
    (net (code "21") (name "MOSI") (class "Default")
      (node (ref "D11") (pin "1") (pinfunction "1_1") (pintype "passive"))
      (node (ref "J1") (pin "14") (pinfunction "14_14") (pintype "bidirectional"))
      (node (ref "J4") (pin "P3") (pinfunction "CMD_P3") (pintype "bidirectional"))
      (node (ref "R7") (pin "1") (pinfunction "1_1") (pintype "passive"))
      (node (ref "TP7") (pin "TP") (pinfunction "TP_TP") (pintype "input"))
      (node (ref "U1") (pin "5") (pinfunction "DI(IO0)_5") (pintype "bidirectional"))
      (node (ref "U2") (pin "7") (pinfunction "IO7_7") (pintype "bidirectional"))
    )
    (net (code "22") (name "Net-(CHG_LED-PadC)") (class "Default")
      (node (ref "CHG_LED") (pin "C") (pinfunction "C_C") (pintype "passive"))
      (node (ref "R1_BAT") (pin "2") (pinfunction "2_2") (pintype "passive"))
    )
    (net (code "23") (name "Net-(D2-CATHODE)") (class "Default")
      (node (ref "C1_BAT1") (pin "1") (pinfunction "1_1") (pintype "passive"))
      (node (ref "D2") (pin "2") (pinfunction "CATHODE_2") (pintype "bidirectional"))
      (node (ref "IC4") (pin "1") (pinfunction "VIN_1") (pintype "bidirectional"))
      (node (ref "IC4") (pin "3") (pinfunction "CE_3") (pintype "bidirectional"))
      (node (ref "Q1") (pin "3") (pinfunction "S_3") (pintype "bidirectional"))
    )
    (net (code "24") (name "Net-(D3-A)") (class "Default")
      (node (ref "C4") (pin "1") (pinfunction "1_1") (pintype "passive"))
      (node (ref "D3") (pin "1") (pinfunction "A_1") (pintype "bidirectional"))
      (node (ref "D4") (pin "2") (pinfunction "K_2") (pintype "bidirectional"))
    )
    (net (code "25") (name "Net-(D7-CATHODE)") (class "Default")
      (node (ref "D7") (pin "2") (pinfunction "CATHODE_2") (pintype "bidirectional"))
      (node (ref "R_CAPACITOR") (pin "2") (pinfunction "2_2") (pintype "passive"))
    )
    (net (code "26") (name "Net-(EPD_C1-Pad1)") (class "Default")
      (node (ref "EPD_C1") (pin "1") (pinfunction "1_1") (pintype "passive"))
      (node (ref "J1") (pin "4") (pinfunction "4_4") (pintype "bidirectional"))
    )
    (net (code "27") (name "Net-(EPD_C2-Pad1)") (class "Default")
      (node (ref "EPD_C2") (pin "1") (pinfunction "1_1") (pintype "passive"))
      (node (ref "J1") (pin "5") (pinfunction "5_5") (pintype "bidirectional"))
    )
    (net (code "28") (name "Net-(EPD_C5-Pad1)") (class "Default")
      (node (ref "EPD_C5") (pin "1") (pinfunction "1_1") (pintype "passive"))
      (node (ref "J1") (pin "15") (pinfunction "15_15") (pintype "bidirectional"))
    )
    (net (code "29") (name "Net-(EPD_C6-Pad1)") (class "Default")
      (node (ref "EPD_C6") (pin "1") (pinfunction "1_1") (pintype "passive"))
      (node (ref "J1") (pin "18") (pinfunction "18_18") (pintype "bidirectional"))
    )
    (net (code "30") (name "Net-(EPD_C7-Pad1)") (class "Default")
      (node (ref "EPD_C7") (pin "1") (pinfunction "1_1") (pintype "passive"))
      (node (ref "J1") (pin "19") (pinfunction "19_19") (pintype "bidirectional"))
    )
    (net (code "31") (name "Net-(EPD_C8-Pad1)") (class "Default")
      (node (ref "EPD_C8") (pin "1") (pinfunction "1_1") (pintype "passive"))
      (node (ref "J1") (pin "20") (pinfunction "20_20") (pintype "bidirectional"))
    )
    (net (code "32") (name "Net-(EPD_C10-Pad1)") (class "Default")
      (node (ref "EPD_C10") (pin "1") (pinfunction "1_1") (pintype "passive"))
      (node (ref "J1") (pin "22") (pinfunction "22_22") (pintype "bidirectional"))
    )
    (net (code "33") (name "Net-(EPD_C12-Pad1)") (class "Default")
      (node (ref "EPD_C12") (pin "1") (pinfunction "1_1") (pintype "passive"))
      (node (ref "J1") (pin "24") (pinfunction "24_24") (pintype "bidirectional"))
    )
    (net (code "34") (name "Net-(IC1-CT)") (class "Default")
      (node (ref "C_DELAY") (pin "1") (pinfunction "1_1") (pintype "passive"))
      (node (ref "IC1") (pin "5") (pinfunction "CT_5") (pintype "bidirectional"))
    )
    (net (code "35") (name "Net-(J2-PadA5)") (class "Default")
      (node (ref "J2") (pin "A5") (pinfunction "A5_A5") (pintype "bidirectional"))
      (node (ref "R2-USB1") (pin "2") (pinfunction "2_2") (pintype "passive"))
    )
    (net (code "36") (name "Net-(J2-PadB5)") (class "Default")
      (node (ref "J2") (pin "B5") (pinfunction "B5_B5") (pintype "bidirectional"))
      (node (ref "R2-USB") (pin "1") (pinfunction "1_1") (pintype "passive"))
    )
    (net (code "37") (name "Net-(MCP73831-PROG)") (class "Default")
      (node (ref "MCP73831") (pin "5") (pinfunction "PROG_5") (pintype "input"))
      (node (ref "R2_BAT") (pin "2") (pinfunction "2_2") (pintype "passive"))
    )
    (net (code "38") (name "Net-(MCP73831-STAT)") (class "Default")
      (node (ref "MCP73831") (pin "1") (pinfunction "STAT_1") (pintype "output"))
      (node (ref "R1_BAT") (pin "1") (pinfunction "1_1") (pintype "passive"))
    )
    (net (code "39") (name "PREVGH") (class "Default")
      (node (ref "D5") (pin "2") (pinfunction "K_2") (pintype "bidirectional"))
      (node (ref "EPD_C9") (pin "1") (pinfunction "1_1") (pintype "passive"))
      (node (ref "J1") (pin "21") (pinfunction "21_21") (pintype "bidirectional"))
    )
    (net (code "40") (name "PREVGL") (class "Default")
      (node (ref "D4") (pin "1") (pinfunction "A_1") (pintype "bidirectional"))
      (node (ref "EPD_C11") (pin "1") (pinfunction "1_1") (pintype "passive"))
      (node (ref "J1") (pin "23") (pinfunction "23_23") (pintype "bidirectional"))
    )
    (net (code "41") (name "RESE") (class "Default")
      (node (ref "J1") (pin "3") (pinfunction "3_3") (pintype "bidirectional"))
      (node (ref "Q3") (pin "2") (pinfunction "S_2") (pintype "bidirectional"))
      (node (ref "R3") (pin "1") (pinfunction "1_1") (pintype "passive"))
    )
    (net (code "42") (name "RESE'") (class "Default")
      (node (ref "R2") (pin "2") (pinfunction "2_2") (pintype "passive"))
      (node (ref "R3") (pin "2") (pinfunction "2_2") (pintype "passive"))
      (node (ref "SJ1") (pin "2") (pinfunction "2_2") (pintype "passive"))
    )
    (net (code "43") (name "RESET") (class "Default")
      (node (ref "C5") (pin "1") (pinfunction "1_1") (pintype "passive"))
      (node (ref "IC1") (pin "1") (pinfunction "VOUT_1") (pintype "bidirectional"))
      (node (ref "RESET_BUTTON") (pin "3") (pinfunction "3_3") (pintype "passive"))
      (node (ref "RESET_BUTTON") (pin "4") (pinfunction "4_4") (pintype "passive"))
      (node (ref "R_RESET") (pin "2") (pinfunction "2_2") (pintype "passive"))
      (node (ref "U2") (pin "3") (pinfunction "EN_3") (pintype "input"))
    )
    (net (code "44") (name "RTC_RST") (class "Default")
      (node (ref "U2") (pin "16") (pinfunction "IO18_16") (pintype "bidirectional"))
      (node (ref "U3") (pin "4") (pinfunction "~{RST}_4") (pintype "input"))
    )
    (net (code "45") (name "RX") (class "Default")
      (node (ref "TP2") (pin "TP") (pinfunction "TP_TP") (pintype "input"))
      (node (ref "U2") (pin "24") (pinfunction "RXD0/GPIO17_24") (pintype "bidirectional"))
    )
    (net (code "46") (name "SCK") (class "Default")
      (node (ref "D10") (pin "1") (pinfunction "1_1") (pintype "passive"))
      (node (ref "J1") (pin "13") (pinfunction "13_13") (pintype "bidirectional"))
      (node (ref "J4") (pin "P5") (pinfunction "CLK_P5") (pintype "bidirectional"))
      (node (ref "R6") (pin "1") (pinfunction "1_1") (pintype "passive"))
      (node (ref "TP8") (pin "TP") (pinfunction "TP_TP") (pintype "input"))
      (node (ref "U1") (pin "6") (pinfunction "CLK_6") (pintype "input"))
      (node (ref "U2") (pin "6") (pinfunction "IO6_6") (pintype "bidirectional"))
    )
    (net (code "47") (name "SCL") (class "Default")
      (node (ref "J3") (pin "4") (pinfunction "4_4") (pintype "passive"))
      (node (ref "R2-PINH") (pin "1") (pinfunction "1_1") (pintype "passive"))
      (node (ref "SENSOR2") (pin "4") (pinfunction "SCK_4") (pintype "input"))
      (node (ref "U2") (pin "20") (pinfunction "IO22_20") (pintype "bidirectional"))
      (node (ref "U3") (pin "16") (pinfunction "SCL_16") (pintype "input"))
      (node (ref "U4") (pin "7") (pinfunction "SCL_7") (pintype "input"))
    )
    (net (code "48") (name "SDA") (class "Default")
      (node (ref "J3") (pin "3") (pinfunction "3_3") (pintype "passive"))
      (node (ref "R1-PINH") (pin "1") (pinfunction "1_1") (pintype "passive"))
      (node (ref "SENSOR2") (pin "3") (pinfunction "SDI_3") (pintype "bidirectional"))
      (node (ref "U2") (pin "19") (pinfunction "IO21_19") (pintype "bidirectional"))
      (node (ref "U3") (pin "15") (pinfunction "SDA_15") (pintype "bidirectional"))
      (node (ref "U4") (pin "8") (pinfunction "SDA_8") (pintype "bidirectional"))
    )
    (net (code "49") (name "SRC") (class "Default")
      (node (ref "C4") (pin "2") (pinfunction "2_2") (pintype "passive"))
      (node (ref "D5") (pin "1") (pinfunction "A_1") (pintype "bidirectional"))
      (node (ref "L1") (pin "1") (pinfunction "1_1") (pintype "passive"))
      (node (ref "Q3") (pin "3") (pinfunction "D_3") (pintype "bidirectional"))
    )
    (net (code "50") (name "SS_SD") (class "Default")
      (node (ref "D8") (pin "1") (pinfunction "1_1") (pintype "passive"))
      (node (ref "J4") (pin "P2") (pinfunction "CD/DAT3_P2") (pintype "bidirectional"))
      (node (ref "R10") (pin "1") (pinfunction "1_1") (pintype "passive"))
      (node (ref "U2") (pin "4") (pinfunction "IO4_4") (pintype "bidirectional"))
    )
    (net (code "51") (name "TX") (class "Default")
      (node (ref "TP1") (pin "TP") (pinfunction "TP_TP") (pintype "input"))
      (node (ref "U2") (pin "25") (pinfunction "TXD0/GPIO16_25") (pintype "bidirectional"))
    )
    (net (code "52") (name "USB_D+") (class "Default")
      (node (ref "D1") (pin "1") (pinfunction "I/O1_1_1") (pintype "bidirectional"))
      (node (ref "U2") (pin "14") (pinfunction "IO13_14") (pintype "bidirectional"))
    )
    (net (code "53") (name "USB_D-") (class "Default")
      (node (ref "D1") (pin "3") (pinfunction "I/O2_1_3") (pintype "bidirectional"))
      (node (ref "U2") (pin "13") (pinfunction "IO12_13") (pintype "bidirectional"))
    )
    (net (code "54") (name "VBAT") (class "Default")
      (node (ref "C2_BAT") (pin "1") (pinfunction "1_1") (pintype "passive"))
      (node (ref "MCP73831") (pin "3") (pinfunction "VBAT_3") (pintype "power_in"))
      (node (ref "Q1") (pin "1") (pinfunction "D_1") (pintype "bidirectional"))
      (node (ref "TP3") (pin "TP") (pinfunction "TP_TP") (pintype "input"))
      (node (ref "U4") (pin "2") (pinfunction "CELL_2") (pintype "power_in"))
      (node (ref "U4") (pin "3") (pinfunction "VDD_3") (pintype "power_in"))
    )
    (net (code "55") (name "VBUS") (class "Default")
      (node (ref "C1_BAT") (pin "1") (pinfunction "1_1") (pintype "passive"))
      (node (ref "C4_USB") (pin "1") (pinfunction "1_1") (pintype "passive"))
      (node (ref "C5_USB") (pin "1") (pinfunction "1_1") (pintype "passive"))
      (node (ref "CHG_LED") (pin "A") (pinfunction "A_A") (pintype "passive"))
      (node (ref "D1") (pin "5") (pinfunction "VBUS_5") (pintype "bidirectional"))
      (node (ref "D2") (pin "1") (pinfunction "ANODE_1") (pintype "bidirectional"))
      (node (ref "MCP73831") (pin "4") (pinfunction "VIN_4") (pintype "power_in"))
      (node (ref "PFMF.050.1") (pin "2") (pinfunction "2_2") (pintype "passive"))
      (node (ref "Q1") (pin "2") (pinfunction "G_2") (pintype "bidirectional"))
      (node (ref "R1_PWRUSB") (pin "2") (pinfunction "2_2") (pintype "passive"))
      (node (ref "TP14") (pin "TP") (pinfunction "TP_TP") (pintype "input"))
    )
    (net (code "56") (name "VRTC") (class "Default")
      (node (ref "C10_SUPERCAP") (pin "2") (pinfunction "2_2") (pintype "passive"))
      (node (ref "C8") (pin "1") (pinfunction "1_1") (pintype "passive"))
      (node (ref "R_CAPACITOR") (pin "1") (pinfunction "1_1") (pintype "passive"))
      (node (ref "U3") (pin "14") (pinfunction "VBAT_14") (pintype "power_in"))
    )
    (net (code "57") (name "VUSB") (class "Default")
      (node (ref "J2") (pin "A4") (pinfunction "A4_A4") (pintype "bidirectional"))
      (node (ref "J2") (pin "A9") (pinfunction "A9_A9") (pintype "bidirectional"))
      (node (ref "J2") (pin "B4") (pinfunction "B4_B4") (pintype "bidirectional"))
      (node (ref "J2") (pin "B9") (pinfunction "B9_B9") (pintype "bidirectional"))
      (node (ref "PFMF.050.1") (pin "1") (pinfunction "1_1") (pintype "passive"))
    )
    (net (code "58") (name "unconnected-(IC1-NC-Pad4)") (class "Default")
      (node (ref "IC1") (pin "4") (pinfunction "NC_4") (pintype "no_connect"))
    )
    (net (code "59") (name "unconnected-(IC4-NC-Pad4)") (class "Default")
      (node (ref "IC4") (pin "4") (pinfunction "NC_4") (pintype "no_connect"))
    )
    (net (code "60") (name "unconnected-(J1-Pad1)") (class "Default")
      (node (ref "J1") (pin "1") (pinfunction "1_1") (pintype "bidirectional"))
    )
    (net (code "61") (name "unconnected-(J1-Pad6)") (class "Default")
      (node (ref "J1") (pin "6") (pinfunction "6_6") (pintype "bidirectional"))
    )
    (net (code "62") (name "unconnected-(J1-Pad7)") (class "Default")
      (node (ref "J1") (pin "7") (pinfunction "7_7") (pintype "bidirectional"))
    )
    (net (code "63") (name "unconnected-(J2-PadA8)") (class "Default")
      (node (ref "J2") (pin "A8") (pinfunction "A8_A8") (pintype "bidirectional"))
    )
    (net (code "64") (name "unconnected-(J2-PadB8)") (class "Default")
      (node (ref "J2") (pin "B8") (pinfunction "B8_B8") (pintype "bidirectional"))
    )
    (net (code "65") (name "unconnected-(J4-DAT1-PadP8)") (class "Default")
      (node (ref "J4") (pin "P8") (pinfunction "DAT1_P8") (pintype "bidirectional"))
    )
    (net (code "66") (name "unconnected-(J4-DAT2-PadP1)") (class "Default")
      (node (ref "J4") (pin "P1") (pinfunction "DAT2_P1") (pintype "bidirectional"))
    )
    (net (code "67") (name "unconnected-(J4-DETECTION_1-PadS1)") (class "Default")
      (node (ref "J4") (pin "S1") (pinfunction "DETECTION_1_S1") (pintype "bidirectional"))
    )
    (net (code "68") (name "unconnected-(J4-DETECTION_2-PadS2)") (class "Default")
      (node (ref "J4") (pin "S2") (pinfunction "DETECTION_2_S2") (pintype "bidirectional"))
    )
    (net (code "69") (name "unconnected-(U2-NC-Pad22)") (class "Default")
      (node (ref "U2") (pin "22") (pinfunction "NC_22") (pintype "no_connect"))
    )
    (net (code "70") (name "unconnected-(U4-~{ALERT}-Pad5)") (class "Default")
      (node (ref "U4") (pin "5") (pinfunction "~{ALERT}_5") (pintype "output"))
    )
  )
)
